# touch.net
KiCad netlist of a schematic drawn in EAGLE
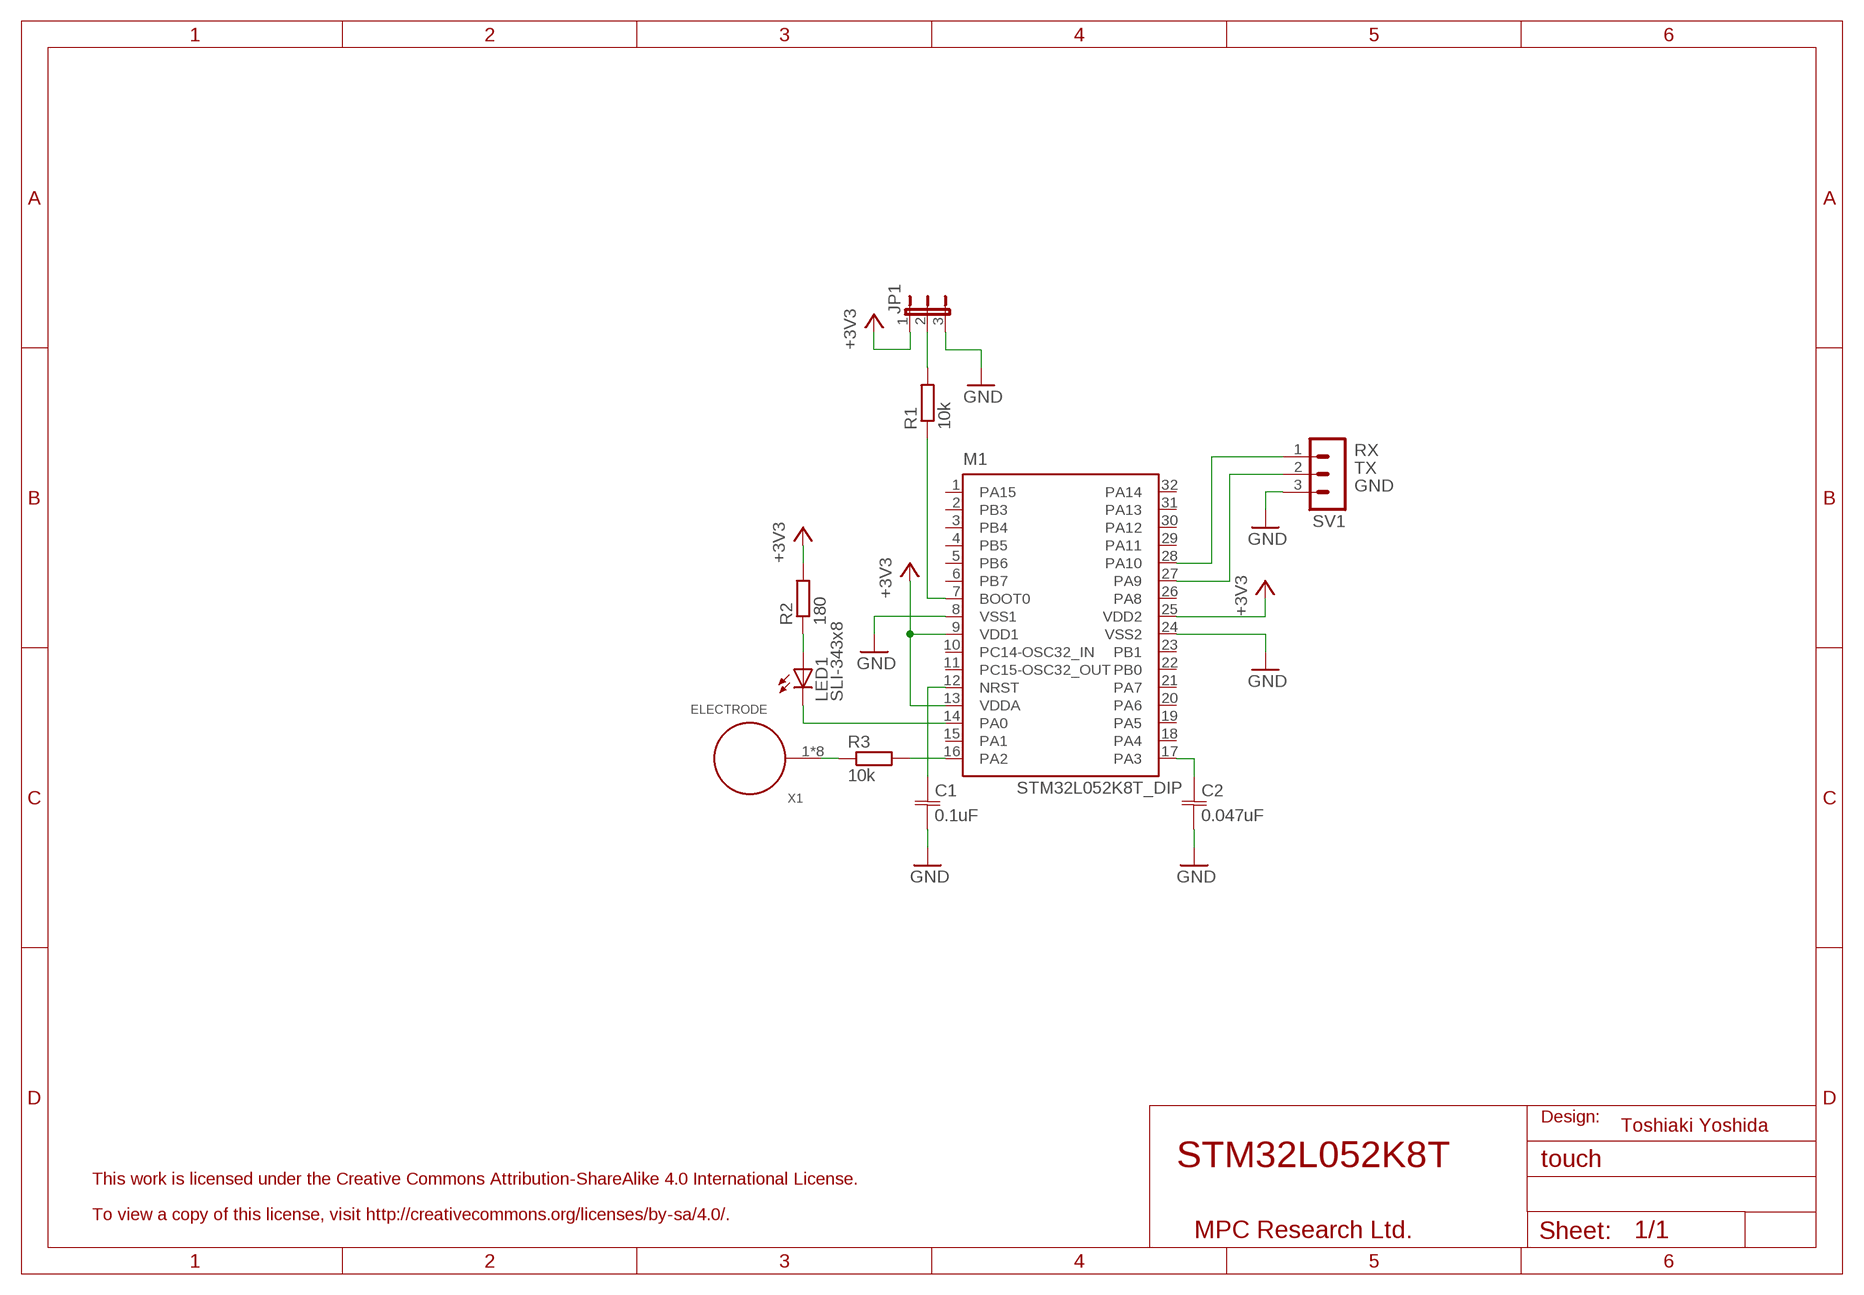
[diagram p0: schematic, sheet 1]

(export (version "E")
  (design (tool "Eeschema 10.0.6"))
  (components
    (comp (ref "C1")
      (value "0.1uF")
      (footprint "eagle-import:C050-024X044")
      (libsource (lib "eagle-import") (part "C-JIS050-024X044"))
    )
    (comp (ref "C2")
      (value "0.047uF")
      (footprint "eagle-import:C050-024X044")
      (libsource (lib "eagle-import") (part "C-JIS050-024X044"))
    )
    (comp (ref "JP1")
      (value "JP2E")
      (footprint "eagle-import:JP2")
      (libsource (lib "eagle-import") (part "JP2E"))
    )
    (comp (ref "LED1")
      (value "SLI-343x8")
      (footprint "eagle-import:LED3MM")
      (libsource (lib "eagle-import") (part "LED3MM"))
    )
    (comp (ref "M1")
      (value "STM32L052K8T_DIP")
      (footprint "eagle-import:DIP32")
      (libsource (lib "eagle-import") (part "STM32L052K8T_DIP"))
    )
    (comp (ref "R1")
      (value "10k")
      (footprint "eagle-import:0207_2V")
      (libsource (lib "eagle-import") (part "R-EU_0207/2V"))
    )
    (comp (ref "R2")
      (value "180")
      (footprint "eagle-import:0207_2V")
      (libsource (lib "eagle-import") (part "R-EU_0207/2V"))
    )
    (comp (ref "R3")
      (value "10k")
      (footprint "eagle-import:0207_10")
      (libsource (lib "eagle-import") (part "R-EU_0207/10"))
    )
    (comp (ref "SV1")
      (value "MA03-1")
      (footprint "eagle-import:MA03-1")
      (libsource (lib "eagle-import") (part "MA03-1"))
    )
    (comp (ref "X1")
      (value "ELECTRODE")
      (footprint "eagle-import:ELECTRODE")
      (libsource (lib "eagle-import") (part "ELECTRODE"))
    )
  )
  (nets
    (net (code "1") (name "+3V3") (class "Default")
      (node (ref "JP1") (pin "1") (pinfunction "1_1") (pintype "passive"))
      (node (ref "M1") (pin "13") (pinfunction "VDDA_13") (pintype "power_in"))
      (node (ref "M1") (pin "25") (pinfunction "VDD2_25") (pintype "bidirectional"))
      (node (ref "M1") (pin "9") (pinfunction "VDD1_9") (pintype "power_in"))
      (node (ref "R2") (pin "2") (pinfunction "2_2") (pintype "passive"))
    )
    (net (code "2") (name "GND") (class "Default")
      (node (ref "C1") (pin "2") (pinfunction "2_2") (pintype "passive"))
      (node (ref "C2") (pin "2") (pinfunction "2_2") (pintype "passive"))
      (node (ref "JP1") (pin "3") (pinfunction "3_3") (pintype "passive"))
      (node (ref "M1") (pin "24") (pinfunction "VSS2_24") (pintype "power_in"))
      (node (ref "M1") (pin "8") (pinfunction "VSS1_8") (pintype "power_in"))
      (node (ref "SV1") (pin "3") (pinfunction "3_3") (pintype "passive"))
    )
    (net (code "3") (name "Net-(JP1-Pad2)") (class "Default")
      (node (ref "JP1") (pin "2") (pinfunction "2_2") (pintype "passive"))
      (node (ref "R1") (pin "2") (pinfunction "2_2") (pintype "passive"))
    )
    (net (code "4") (name "Net-(LED1-C)") (class "Default")
      (node (ref "LED1") (pin "K") (pinfunction "C_K") (pintype "passive"))
      (node (ref "M1") (pin "14") (pinfunction "PA0_14") (pintype "bidirectional"))
    )
    (net (code "5") (name "Net-(LED1-PadA)") (class "Default")
      (node (ref "LED1") (pin "A") (pinfunction "A_A") (pintype "passive"))
      (node (ref "R2") (pin "1") (pinfunction "1_1") (pintype "passive"))
    )
    (net (code "6") (name "Net-(M1-BOOT0)") (class "Default")
      (node (ref "M1") (pin "7") (pinfunction "BOOT0_7") (pintype "bidirectional"))
      (node (ref "R1") (pin "1") (pinfunction "1_1") (pintype "passive"))
    )
    (net (code "7") (name "Net-(M1-NRST)") (class "Default")
      (node (ref "C1") (pin "1") (pinfunction "1_1") (pintype "passive"))
      (node (ref "M1") (pin "12") (pinfunction "NRST_12") (pintype "bidirectional"))
    )
    (net (code "8") (name "Net-(M1-PA2)") (class "Default")
      (node (ref "M1") (pin "16") (pinfunction "PA2_16") (pintype "bidirectional"))
      (node (ref "R3") (pin "2") (pinfunction "2_2") (pintype "passive"))
    )
    (net (code "9") (name "Net-(M1-PA3)") (class "Default")
      (node (ref "C2") (pin "1") (pinfunction "1_1") (pintype "passive"))
      (node (ref "M1") (pin "17") (pinfunction "PA3_17") (pintype "bidirectional"))
    )
    (net (code "10") (name "Net-(M1-PA9)") (class "Default")
      (node (ref "M1") (pin "27") (pinfunction "PA9_27") (pintype "bidirectional"))
      (node (ref "SV1") (pin "2") (pinfunction "2_2") (pintype "passive"))
    )
    (net (code "11") (name "Net-(M1-PA10)") (class "Default")
      (node (ref "M1") (pin "28") (pinfunction "PA10_28") (pintype "bidirectional"))
      (node (ref "SV1") (pin "1") (pinfunction "1_1") (pintype "passive"))
    )
    (net (code "12") (name "Net-(R3-Pad1)") (class "Default")
      (node (ref "R3") (pin "1") (pinfunction "1_1") (pintype "passive"))
      (node (ref "X1") (pin "1") (pinfunction "1_1") (pintype "passive"))
      (node (ref "X1") (pin "2") (pinfunction "1_2") (pintype "passive"))
      (node (ref "X1") (pin "3") (pinfunction "1_3") (pintype "passive"))
      (node (ref "X1") (pin "4") (pinfunction "1_4") (pintype "passive"))
      (node (ref "X1") (pin "5") (pinfunction "1_5") (pintype "passive"))
      (node (ref "X1") (pin "6") (pinfunction "1_6") (pintype "passive"))
      (node (ref "X1") (pin "7") (pinfunction "1_7") (pintype "passive"))
      (node (ref "X1") (pin "8") (pinfunction "1_8") (pintype "passive"))
    )
    (net (code "13") (name "unconnected-(M1-PA1-Pad15)") (class "Default")
      (node (ref "M1") (pin "15") (pinfunction "PA1_15") (pintype "bidirectional"))
    )
    (net (code "14") (name "unconnected-(M1-PA4-Pad18)") (class "Default")
      (node (ref "M1") (pin "18") (pinfunction "PA4_18") (pintype "bidirectional"))
    )
    (net (code "15") (name "unconnected-(M1-PA5-Pad19)") (class "Default")
      (node (ref "M1") (pin "19") (pinfunction "PA5_19") (pintype "bidirectional"))
    )
    (net (code "16") (name "unconnected-(M1-PA6-Pad20)") (class "Default")
      (node (ref "M1") (pin "20") (pinfunction "PA6_20") (pintype "bidirectional"))
    )
    (net (code "17") (name "unconnected-(M1-PA7-Pad21)") (class "Default")
      (node (ref "M1") (pin "21") (pinfunction "PA7_21") (pintype "bidirectional"))
    )
    (net (code "18") (name "unconnected-(M1-PA8-Pad26)") (class "Default")
      (node (ref "M1") (pin "26") (pinfunction "PA8_26") (pintype "bidirectional"))
    )
    (net (code "19") (name "unconnected-(M1-PA11-Pad29)") (class "Default")
      (node (ref "M1") (pin "29") (pinfunction "PA11_29") (pintype "bidirectional"))
    )
    (net (code "20") (name "unconnected-(M1-PA12-Pad30)") (class "Default")
      (node (ref "M1") (pin "30") (pinfunction "PA12_30") (pintype "bidirectional"))
    )
    (net (code "21") (name "unconnected-(M1-PA13-Pad31)") (class "Default")
      (node (ref "M1") (pin "31") (pinfunction "PA13_31") (pintype "bidirectional"))
    )
    (net (code "22") (name "unconnected-(M1-PA14-Pad32)") (class "Default")
      (node (ref "M1") (pin "32") (pinfunction "PA14_32") (pintype "bidirectional"))
    )
    (net (code "23") (name "unconnected-(M1-PA15-Pad1)") (class "Default")
      (node (ref "M1") (pin "1") (pinfunction "PA15_1") (pintype "bidirectional"))
    )
    (net (code "24") (name "unconnected-(M1-PB0-Pad22)") (class "Default")
      (node (ref "M1") (pin "22") (pinfunction "PB0_22") (pintype "bidirectional"))
    )
    (net (code "25") (name "unconnected-(M1-PB1-Pad23)") (class "Default")
      (node (ref "M1") (pin "23") (pinfunction "PB1_23") (pintype "bidirectional"))
    )
    (net (code "26") (name "unconnected-(M1-PB3-Pad2)") (class "Default")
      (node (ref "M1") (pin "2") (pinfunction "PB3_2") (pintype "bidirectional"))
    )
    (net (code "27") (name "unconnected-(M1-PB4-Pad3)") (class "Default")
      (node (ref "M1") (pin "3") (pinfunction "PB4_3") (pintype "bidirectional"))
    )
    (net (code "28") (name "unconnected-(M1-PB5-Pad4)") (class "Default")
      (node (ref "M1") (pin "4") (pinfunction "PB5_4") (pintype "bidirectional"))
    )
    (net (code "29") (name "unconnected-(M1-PB6-Pad5)") (class "Default")
      (node (ref "M1") (pin "5") (pinfunction "PB6_5") (pintype "bidirectional"))
    )
    (net (code "30") (name "unconnected-(M1-PB7-Pad6)") (class "Default")
      (node (ref "M1") (pin "6") (pinfunction "PB7_6") (pintype "bidirectional"))
    )
    (net (code "31") (name "unconnected-(M1-PC14-OSC32_IN-Pad10)") (class "Default")
      (node (ref "M1") (pin "10") (pinfunction "PC14-OSC32_IN_10") (pintype "bidirectional"))
    )
    (net (code "32") (name "unconnected-(M1-PC15-OSC32_OUT-Pad11)") (class "Default")
      (node (ref "M1") (pin "11") (pinfunction "PC15-OSC32_OUT_11") (pintype "bidirectional"))
    )
  )
)
